# TopLevel.net
KiCad netlist of a schematic drawn in Altium Designer
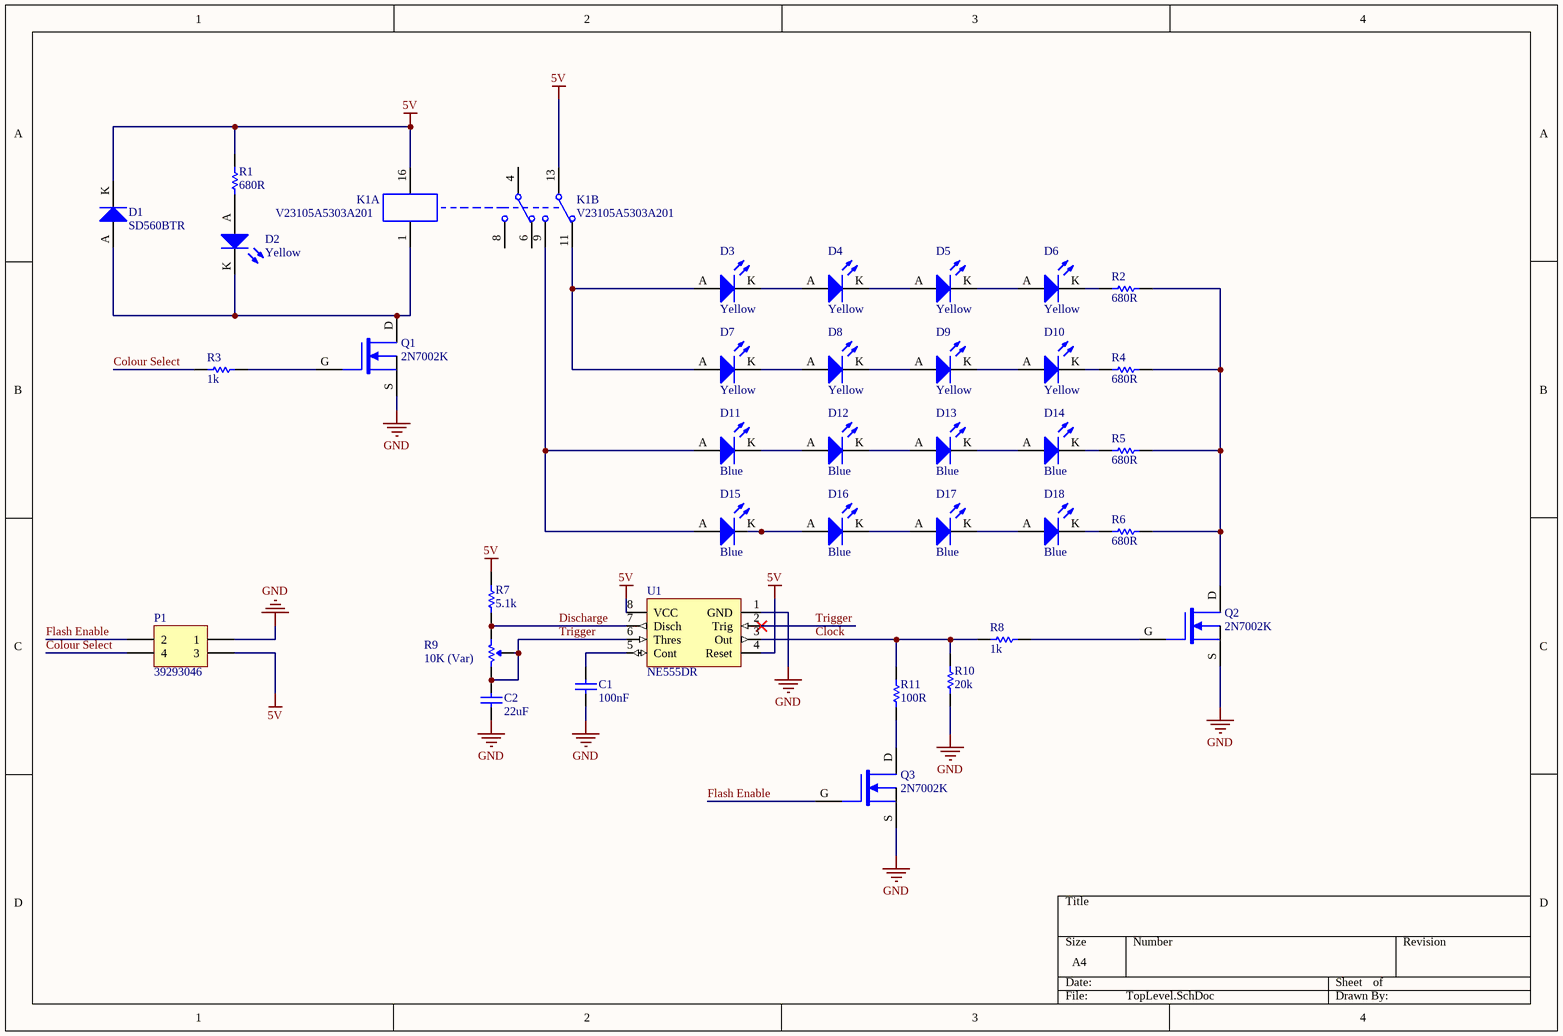
[diagram p0: TopLevel.SchDoc]

(export (version "E")
  (design (tool "Eeschema 10.0.6"))
  (components
    (comp (ref "C1")
      (value "100nF")
      (footprint "0805")
      (fields
        (field (name "PART NUMBER") "GCM21BR71H104KA37L")
        (field (name "TOLERANCE") "±10%")
        (field (name "MANUFACTURER") "muRata")
      )
      (libsource (lib "ts_20-standard-library") (part "Capacitor"))
    )
    (comp (ref "C2")
      (value "22uF")
      (footprint "1206")
      (fields
        (field (name "PART NUMBER") "CC1206MKX5R7BB226")
        (field (name "TOLERANCE") "20%")
        (field (name "MANUFACTURER") "YAGEO")
      )
      (libsource (lib "ts_20-standard-library") (part "Capacitor"))
    )
    (comp (ref "D1")
      (value "SD560BTR")
      (footprint "SMB Diode")
      (description "1.2V_F 600V 5A SMB")
      (fields
        (field (name "MANUFACTURER") "SMC Diode Solutions")
        (field (name "DIGIKEY PART NUMBER") "1655-1530-2-ND")
      )
      (libsource (lib "ts_20-standard-library") (part "Diode"))
    )
    (comp (ref "D2")
      (value "Yellow")
      (footprint "0805 LED")
      (description "Yellow LED Indication - Discrete 1.75V 0805 (2012 Metric)")
      (fields (field (name "PART NUMBER") "SML-211YTT86") (field (name "MANUFACTURER") "ROHM Semiconductor"))
      (libsource (lib "ts_20-standard-library") (part "LED"))
    )
    (comp (ref "D3")
      (value "Yellow")
      (footprint "0805 LED")
      (description "Yellow LED Indication - Discrete 1.75V 0805 (2012 Metric)")
      (fields (field (name "PART NUMBER") "SML-211YTT86") (field (name "MANUFACTURER") "ROHM Semiconductor"))
      (libsource (lib "ts_20-standard-library") (part "LED"))
    )
    (comp (ref "D4")
      (value "Yellow")
      (footprint "0805 LED")
      (description "Yellow LED Indication - Discrete 1.75V 0805 (2012 Metric)")
      (fields (field (name "PART NUMBER") "SML-211YTT86") (field (name "MANUFACTURER") "ROHM Semiconductor"))
      (libsource (lib "ts_20-standard-library") (part "LED"))
    )
    (comp (ref "D5")
      (value "Yellow")
      (footprint "0805 LED")
      (description "Yellow LED Indication - Discrete 1.75V 0805 (2012 Metric)")
      (fields (field (name "PART NUMBER") "SML-211YTT86") (field (name "MANUFACTURER") "ROHM Semiconductor"))
      (libsource (lib "ts_20-standard-library") (part "LED"))
    )
    (comp (ref "D6")
      (value "Yellow")
      (footprint "0805 LED")
      (description "Yellow LED Indication - Discrete 1.75V 0805 (2012 Metric)")
      (fields (field (name "PART NUMBER") "SML-211YTT86") (field (name "MANUFACTURER") "ROHM Semiconductor"))
      (libsource (lib "ts_20-standard-library") (part "LED"))
    )
    (comp (ref "D7")
      (value "Yellow")
      (footprint "0805 LED")
      (description "Yellow LED Indication - Discrete 1.75V 0805 (2012 Metric)")
      (fields (field (name "PART NUMBER") "SML-211YTT86") (field (name "MANUFACTURER") "ROHM Semiconductor"))
      (libsource (lib "ts_20-standard-library") (part "LED"))
    )
    (comp (ref "D8")
      (value "Yellow")
      (footprint "0805 LED")
      (description "Yellow LED Indication - Discrete 1.75V 0805 (2012 Metric)")
      (fields (field (name "PART NUMBER") "SML-211YTT86") (field (name "MANUFACTURER") "ROHM Semiconductor"))
      (libsource (lib "ts_20-standard-library") (part "LED"))
    )
    (comp (ref "D9")
      (value "Yellow")
      (footprint "0805 LED")
      (description "Yellow LED Indication - Discrete 1.75V 0805 (2012 Metric)")
      (fields (field (name "PART NUMBER") "SML-211YTT86") (field (name "MANUFACTURER") "ROHM Semiconductor"))
      (libsource (lib "ts_20-standard-library") (part "LED"))
    )
    (comp (ref "D10")
      (value "Yellow")
      (footprint "0805 LED")
      (description "Yellow LED Indication - Discrete 1.75V 0805 (2012 Metric)")
      (fields (field (name "PART NUMBER") "SML-211YTT86") (field (name "MANUFACTURER") "ROHM Semiconductor"))
      (libsource (lib "ts_20-standard-library") (part "LED"))
    )
    (comp (ref "D11")
      (value "Blue")
      (footprint "0805 LED")
      (description "LED BLUE CLEAR 2012 SMD")
      (fields
        (field (name "PART NUMBER") "SML-MN2BCTT86C")
        (field (name "MANUFACTURER") "ROHM Semiconductor")
      )
      (libsource (lib "ts_20-standard-library") (part "LED"))
    )
    (comp (ref "D12")
      (value "Blue")
      (footprint "0805 LED")
      (description "LED BLUE CLEAR 2012 SMD")
      (fields
        (field (name "PART NUMBER") "SML-MN2BCTT86C")
        (field (name "MANUFACTURER") "ROHM Semiconductor")
      )
      (libsource (lib "ts_20-standard-library") (part "LED"))
    )
    (comp (ref "D13")
      (value "Blue")
      (footprint "0805 LED")
      (description "LED BLUE CLEAR 2012 SMD")
      (fields
        (field (name "PART NUMBER") "SML-MN2BCTT86C")
        (field (name "MANUFACTURER") "ROHM Semiconductor")
      )
      (libsource (lib "ts_20-standard-library") (part "LED"))
    )
    (comp (ref "D14")
      (value "Blue")
      (footprint "0805 LED")
      (description "LED BLUE CLEAR 2012 SMD")
      (fields
        (field (name "PART NUMBER") "SML-MN2BCTT86C")
        (field (name "MANUFACTURER") "ROHM Semiconductor")
      )
      (libsource (lib "ts_20-standard-library") (part "LED"))
    )
    (comp (ref "D15")
      (value "Blue")
      (footprint "0805 LED")
      (description "LED BLUE CLEAR 2012 SMD")
      (fields
        (field (name "PART NUMBER") "SML-MN2BCTT86C")
        (field (name "MANUFACTURER") "ROHM Semiconductor")
      )
      (libsource (lib "ts_20-standard-library") (part "LED"))
    )
    (comp (ref "D16")
      (value "Blue")
      (footprint "0805 LED")
      (description "LED BLUE CLEAR 2012 SMD")
      (fields
        (field (name "PART NUMBER") "SML-MN2BCTT86C")
        (field (name "MANUFACTURER") "ROHM Semiconductor")
      )
      (libsource (lib "ts_20-standard-library") (part "LED"))
    )
    (comp (ref "D17")
      (value "Blue")
      (footprint "0805 LED")
      (description "LED BLUE CLEAR 2012 SMD")
      (fields
        (field (name "PART NUMBER") "SML-MN2BCTT86C")
        (field (name "MANUFACTURER") "ROHM Semiconductor")
      )
      (libsource (lib "ts_20-standard-library") (part "LED"))
    )
    (comp (ref "D18")
      (value "Blue")
      (footprint "0805 LED")
      (description "LED BLUE CLEAR 2012 SMD")
      (fields
        (field (name "PART NUMBER") "SML-MN2BCTT86C")
        (field (name "MANUFACTURER") "ROHM Semiconductor")
      )
      (libsource (lib "ts_20-standard-library") (part "LED"))
    )
    (comp (ref "K1")
      (value "V23105A5303A201")
      (footprint "TI 2-DIL")
      (description "RELAY TELECOM DPDT 3A 12V")
      (fields (field (name "MANUFACTURER") "TE Connectivity") (field (name "DIGIKEY PART NUMBER") "PB387-ND"))
      (libsource (lib "") (part "V23105A5303A201_1"))
    )
    (comp (ref "P1")
      (value "39293046")
      (footprint "39293046")
      (fields (field (name "DIGIKEY PART NUMBER") "WM3844-ND") (field (name "CONTACT") "Tin"))
      (libsource (lib "ts_20-standard-connectors") (part "4"))
    )
    (comp (ref "Q1")
      (value "2N7002K")
      (footprint "ON SOT-23 MOSFET")
      (description "60V 380mA, NFET MOSTFET (Small Signal)")
      (fields
        (field (name "MANUFACTURER") "ON Semiconductor")
        (field (name "DIGIKEY PART NUMBER") "2N7002KCT-ND")
        (field (name "PUBLISHER") "Altium Limited")
      )
      (libsource (lib "ts_20-standard-library") (part "MOSFET-N"))
    )
    (comp (ref "Q2")
      (value "2N7002K")
      (footprint "ON SOT-23 MOSFET")
      (description "60V 380mA, NFET MOSTFET (Small Signal)")
      (fields
        (field (name "MANUFACTURER") "ON Semiconductor")
        (field (name "DIGIKEY PART NUMBER") "2N7002KCT-ND")
        (field (name "PUBLISHER") "Altium Limited")
      )
      (libsource (lib "ts_20-standard-library") (part "MOSFET-N"))
    )
    (comp (ref "Q3")
      (value "2N7002K")
      (footprint "ON SOT-23 MOSFET")
      (description "60V 380mA, NFET MOSTFET (Small Signal)")
      (fields
        (field (name "MANUFACTURER") "ON Semiconductor")
        (field (name "DIGIKEY PART NUMBER") "2N7002KCT-ND")
        (field (name "PUBLISHER") "Altium Limited")
      )
      (libsource (lib "ts_20-standard-library") (part "MOSFET-N"))
    )
    (comp (ref "R1")
      (value "680R")
      (footprint "0805")
      (fields
        (field (name "PART NUMBER") "RC0805FR07680RL")
        (field (name "MANUFACTURER") "YAGEO")
        (field (name "TOLERANCE") "0.01")
      )
      (libsource (lib "ts_20-standard-library") (part "Resistor"))
    )
    (comp (ref "R2")
      (value "680R")
      (footprint "0805")
      (fields
        (field (name "PART NUMBER") "RC0805FR07680RL")
        (field (name "MANUFACTURER") "YAGEO")
        (field (name "TOLERANCE") "0.01")
      )
      (libsource (lib "ts_20-standard-library") (part "Resistor"))
    )
    (comp (ref "R3")
      (value "1k")
      (footprint "0805")
      (fields
        (field (name "PART NUMBER") "RC0805FR071KL")
        (field (name "MANUFACTURER") "YAGEO")
        (field (name "TOLERANCE") "0.01")
      )
      (libsource (lib "ts_20-standard-library") (part "Resistor"))
    )
    (comp (ref "R4")
      (value "680R")
      (footprint "0805")
      (fields
        (field (name "PART NUMBER") "RC0805FR07680RL")
        (field (name "MANUFACTURER") "YAGEO")
        (field (name "TOLERANCE") "0.01")
      )
      (libsource (lib "ts_20-standard-library") (part "Resistor"))
    )
    (comp (ref "R5")
      (value "680R")
      (footprint "0805")
      (fields
        (field (name "PART NUMBER") "RC0805FR07680RL")
        (field (name "MANUFACTURER") "YAGEO")
        (field (name "TOLERANCE") "0.01")
      )
      (libsource (lib "ts_20-standard-library") (part "Resistor"))
    )
    (comp (ref "R6")
      (value "680R")
      (footprint "0805")
      (fields
        (field (name "PART NUMBER") "RC0805FR07680RL")
        (field (name "MANUFACTURER") "YAGEO")
        (field (name "TOLERANCE") "0.01")
      )
      (libsource (lib "ts_20-standard-library") (part "Resistor"))
    )
    (comp (ref "R7")
      (value "5.1k")
      (footprint "0805")
      (fields
        (field (name "PART NUMBER") "RC0805FR075K1L")
        (field (name "MANUFACTURER") "YAGEO")
        (field (name "TOLERANCE") "0.01")
      )
      (libsource (lib "ts_20-standard-library") (part "Resistor"))
    )
    (comp (ref "R8")
      (value "1k")
      (footprint "0805")
      (fields
        (field (name "PART NUMBER") "RC0805FR071KL")
        (field (name "MANUFACTURER") "YAGEO")
        (field (name "TOLERANCE") "0.01")
      )
      (libsource (lib "ts_20-standard-library") (part "Resistor"))
    )
    (comp (ref "R9")
      (value "10K (Var)")
      (footprint "B 3296")
      (fields
        (field (name "PART NUMBER") "3296W-1-103LF")
        (field (name "MANUFACTURER") "Bournes Inc")
        (field (name "TOLERANCE") "0.1")
      )
      (libsource (lib "ts_20-standard-library") (part "Resistor (Potentiometer)"))
    )
    (comp (ref "R10")
      (value "20k")
      (footprint "0805")
      (fields
        (field (name "PART NUMBER") "RC0805FR0720KL")
        (field (name "MANUFACTURER") "YAGEO")
        (field (name "TOLERANCE") "0.01")
      )
      (libsource (lib "ts_20-standard-library") (part "Resistor"))
    )
    (comp (ref "R11")
      (value "100R")
      (footprint "0805")
      (fields
        (field (name "PART NUMBER") "RC0805FR071KL")
        (field (name "MANUFACTURER") "YAGEO")
        (field (name "TOLERANCE") "0.01")
      )
      (libsource (lib "ts_20-standard-library") (part "Resistor"))
    )
    (comp (ref "U1")
      (value "NE555DR")
      (footprint "TI 8-SOIC")
      (description "IC OSC SGL TIMER 100KHZ 8-SOIC")
      (fields
        (field (name "MANUFACTURER") "Texas Instruments")
        (field (name "DIGIKEY PART NUMBER") "296-6501-1-ND")
      )
      (libsource (lib "ts_20-standard-library") (part "NE555DR"))
    )
  )
  (nets
    (net (code "1") (name "/Clock") (class "Default")
      (node (ref "R10") (pin "2") (pinfunction "2_2") (pintype "passive"))
      (node (ref "R11") (pin "2") (pinfunction "2_2") (pintype "passive"))
      (node (ref "R8") (pin "1") (pinfunction "1_1") (pintype "passive"))
      (node (ref "U1") (pin "3") (pinfunction "Out_3") (pintype "output"))
    )
    (net (code "2") (name "/Colour Select") (class "Default")
      (node (ref "P1") (pin "4") (pinfunction "4_4") (pintype "passive"))
      (node (ref "R3") (pin "1") (pinfunction "1_1") (pintype "passive"))
    )
    (net (code "3") (name "/Discharge") (class "Default")
      (node (ref "R7") (pin "1") (pinfunction "1_1") (pintype "passive"))
      (node (ref "R9") (pin "3") (pinfunction "CW_3") (pintype "passive"))
      (node (ref "U1") (pin "7") (pinfunction "Disch_7") (pintype "output"))
    )
    (net (code "4") (name "/Flash Enable") (class "Default")
      (node (ref "P1") (pin "2") (pinfunction "2_2") (pintype "passive"))
      (node (ref "Q3") (pin "G") (pinfunction "G_G") (pintype "passive"))
    )
    (net (code "5") (name "/Trigger") (class "Default")
      (node (ref "C2") (pin "2") (pinfunction "2_2") (pintype "passive"))
      (node (ref "R9") (pin "1") (pinfunction "CCW_1") (pintype "passive"))
      (node (ref "R9") (pin "2") (pinfunction "Wiper_2") (pintype "passive"))
      (node (ref "U1") (pin "2") (pinfunction "Trig_2") (pintype "input"))
      (node (ref "U1") (pin "6") (pinfunction "Thres_6") (pintype "input"))
    )
    (net (code "6") (name "5V") (class "Default")
      (node (ref "D1") (pin "K") (pinfunction "K_K") (pintype "passive"))
      (node (ref "K1") (pin "13") (pinfunction "13_13") (pintype "passive"))
      (node (ref "K1") (pin "16") (pinfunction "16_16") (pintype "passive"))
      (node (ref "P1") (pin "3") (pinfunction "3_3") (pintype "passive"))
      (node (ref "R1") (pin "2") (pinfunction "2_2") (pintype "passive"))
      (node (ref "R7") (pin "2") (pinfunction "2_2") (pintype "passive"))
      (node (ref "U1") (pin "4") (pinfunction "Reset_4") (pintype "passive"))
      (node (ref "U1") (pin "8") (pinfunction "VCC_8") (pintype "passive"))
    )
    (net (code "7") (name "GND") (class "Default")
      (node (ref "C1") (pin "1") (pinfunction "1_1") (pintype "passive"))
      (node (ref "C2") (pin "1") (pinfunction "1_1") (pintype "passive"))
      (node (ref "P1") (pin "1") (pinfunction "1_1") (pintype "passive"))
      (node (ref "Q1") (pin "S") (pinfunction "S_S") (pintype "passive"))
      (node (ref "Q2") (pin "S") (pinfunction "S_S") (pintype "passive"))
      (node (ref "Q3") (pin "S") (pinfunction "S_S") (pintype "passive"))
      (node (ref "R10") (pin "1") (pinfunction "1_1") (pintype "passive"))
      (node (ref "U1") (pin "1") (pinfunction "GND_1") (pintype "power_in"))
    )
    (net (code "8") (name "Net-(D1-PadA)") (class "Default")
      (node (ref "D1") (pin "A") (pinfunction "A_A") (pintype "passive"))
      (node (ref "D2") (pin "K") (pinfunction "K_K") (pintype "passive"))
      (node (ref "K1") (pin "1") (pinfunction "1_1") (pintype "passive"))
      (node (ref "Q1") (pin "D") (pinfunction "D_D") (pintype "passive"))
    )
    (net (code "9") (name "Net-(D2-PadA)") (class "Default")
      (node (ref "D2") (pin "A") (pinfunction "A_A") (pintype "passive"))
      (node (ref "R1") (pin "1") (pinfunction "1_1") (pintype "passive"))
    )
    (net (code "10") (name "Net-(D3-PadA)") (class "Default")
      (node (ref "D3") (pin "A") (pinfunction "A_A") (pintype "passive"))
      (node (ref "D7") (pin "A") (pinfunction "A_A") (pintype "passive"))
      (node (ref "K1") (pin "11") (pinfunction "11_11") (pintype "passive"))
    )
    (net (code "11") (name "Net-(D3-PadK)") (class "Default")
      (node (ref "D3") (pin "K") (pinfunction "K_K") (pintype "passive"))
      (node (ref "D4") (pin "A") (pinfunction "A_A") (pintype "passive"))
    )
    (net (code "12") (name "Net-(D4-PadK)") (class "Default")
      (node (ref "D4") (pin "K") (pinfunction "K_K") (pintype "passive"))
      (node (ref "D5") (pin "A") (pinfunction "A_A") (pintype "passive"))
    )
    (net (code "13") (name "Net-(D5-PadK)") (class "Default")
      (node (ref "D5") (pin "K") (pinfunction "K_K") (pintype "passive"))
      (node (ref "D6") (pin "A") (pinfunction "A_A") (pintype "passive"))
    )
    (net (code "14") (name "Net-(D6-PadK)") (class "Default")
      (node (ref "D6") (pin "K") (pinfunction "K_K") (pintype "passive"))
      (node (ref "R2") (pin "1") (pinfunction "1_1") (pintype "passive"))
    )
    (net (code "15") (name "Net-(D7-PadK)") (class "Default")
      (node (ref "D7") (pin "K") (pinfunction "K_K") (pintype "passive"))
      (node (ref "D8") (pin "A") (pinfunction "A_A") (pintype "passive"))
    )
    (net (code "16") (name "Net-(D8-PadK)") (class "Default")
      (node (ref "D8") (pin "K") (pinfunction "K_K") (pintype "passive"))
      (node (ref "D9") (pin "A") (pinfunction "A_A") (pintype "passive"))
    )
    (net (code "17") (name "Net-(D10-PadA)") (class "Default")
      (node (ref "D10") (pin "A") (pinfunction "A_A") (pintype "passive"))
      (node (ref "D9") (pin "K") (pinfunction "K_K") (pintype "passive"))
    )
    (net (code "18") (name "Net-(D10-PadK)") (class "Default")
      (node (ref "D10") (pin "K") (pinfunction "K_K") (pintype "passive"))
      (node (ref "R4") (pin "1") (pinfunction "1_1") (pintype "passive"))
    )
    (net (code "19") (name "Net-(D11-PadA)") (class "Default")
      (node (ref "D11") (pin "A") (pinfunction "A_A") (pintype "passive"))
      (node (ref "D15") (pin "A") (pinfunction "A_A") (pintype "passive"))
      (node (ref "K1") (pin "9") (pinfunction "9_9") (pintype "passive"))
    )
    (net (code "20") (name "Net-(D11-PadK)") (class "Default")
      (node (ref "D11") (pin "K") (pinfunction "K_K") (pintype "passive"))
      (node (ref "D12") (pin "A") (pinfunction "A_A") (pintype "passive"))
    )
    (net (code "21") (name "Net-(D12-PadK)") (class "Default")
      (node (ref "D12") (pin "K") (pinfunction "K_K") (pintype "passive"))
      (node (ref "D13") (pin "A") (pinfunction "A_A") (pintype "passive"))
    )
    (net (code "22") (name "Net-(D13-PadK)") (class "Default")
      (node (ref "D13") (pin "K") (pinfunction "K_K") (pintype "passive"))
      (node (ref "D14") (pin "A") (pinfunction "A_A") (pintype "passive"))
    )
    (net (code "23") (name "Net-(D14-PadK)") (class "Default")
      (node (ref "D14") (pin "K") (pinfunction "K_K") (pintype "passive"))
      (node (ref "R5") (pin "1") (pinfunction "1_1") (pintype "passive"))
    )
    (net (code "24") (name "Net-(D15-PadK)") (class "Default")
      (node (ref "D15") (pin "K") (pinfunction "K_K") (pintype "passive"))
      (node (ref "D16") (pin "A") (pinfunction "A_A") (pintype "passive"))
    )
    (net (code "25") (name "Net-(D16-PadK)") (class "Default")
      (node (ref "D16") (pin "K") (pinfunction "K_K") (pintype "passive"))
      (node (ref "D17") (pin "A") (pinfunction "A_A") (pintype "passive"))
    )
    (net (code "26") (name "Net-(D17-PadK)") (class "Default")
      (node (ref "D17") (pin "K") (pinfunction "K_K") (pintype "passive"))
      (node (ref "D18") (pin "A") (pinfunction "A_A") (pintype "passive"))
    )
    (net (code "27") (name "Net-(D18-PadK)") (class "Default")
      (node (ref "D18") (pin "K") (pinfunction "K_K") (pintype "passive"))
      (node (ref "R6") (pin "1") (pinfunction "1_1") (pintype "passive"))
    )
    (net (code "28") (name "Net-(Q1-PadG)") (class "Default")
      (node (ref "Q1") (pin "G") (pinfunction "G_G") (pintype "passive"))
      (node (ref "R3") (pin "2") (pinfunction "2_2") (pintype "passive"))
    )
    (net (code "29") (name "Net-(Q2-PadD)") (class "Default")
      (node (ref "Q2") (pin "D") (pinfunction "D_D") (pintype "passive"))
      (node (ref "R2") (pin "2") (pinfunction "2_2") (pintype "passive"))
      (node (ref "R4") (pin "2") (pinfunction "2_2") (pintype "passive"))
      (node (ref "R5") (pin "2") (pinfunction "2_2") (pintype "passive"))
      (node (ref "R6") (pin "2") (pinfunction "2_2") (pintype "passive"))
    )
    (net (code "30") (name "Net-(Q2-PadG)") (class "Default")
      (node (ref "Q2") (pin "G") (pinfunction "G_G") (pintype "passive"))
      (node (ref "R8") (pin "2") (pinfunction "2_2") (pintype "passive"))
    )
    (net (code "31") (name "Net-(Q3-PadD)") (class "Default")
      (node (ref "Q3") (pin "D") (pinfunction "D_D") (pintype "passive"))
      (node (ref "R11") (pin "1") (pinfunction "1_1") (pintype "passive"))
    )
    (net (code "32") (name "Net-(U1-Cont)") (class "Default")
      (node (ref "C1") (pin "2") (pinfunction "2_2") (pintype "passive"))
      (node (ref "U1") (pin "5") (pinfunction "Cont_5") (pintype "bidirectional"))
    )
    (net (code "33") (name "unconnected-(K1-Pad4)") (class "Default")
      (node (ref "K1") (pin "4") (pinfunction "4_4") (pintype "passive"))
    )
    (net (code "34") (name "unconnected-(K1-Pad6)") (class "Default")
      (node (ref "K1") (pin "6") (pinfunction "6_6") (pintype "passive"))
    )
    (net (code "35") (name "unconnected-(K1-Pad8)") (class "Default")
      (node (ref "K1") (pin "8") (pinfunction "8_8") (pintype "passive"))
    )
  )
)
